# DigitalLabBoard_Traffic.net
KiCad netlist of a schematic drawn in Altium Designer
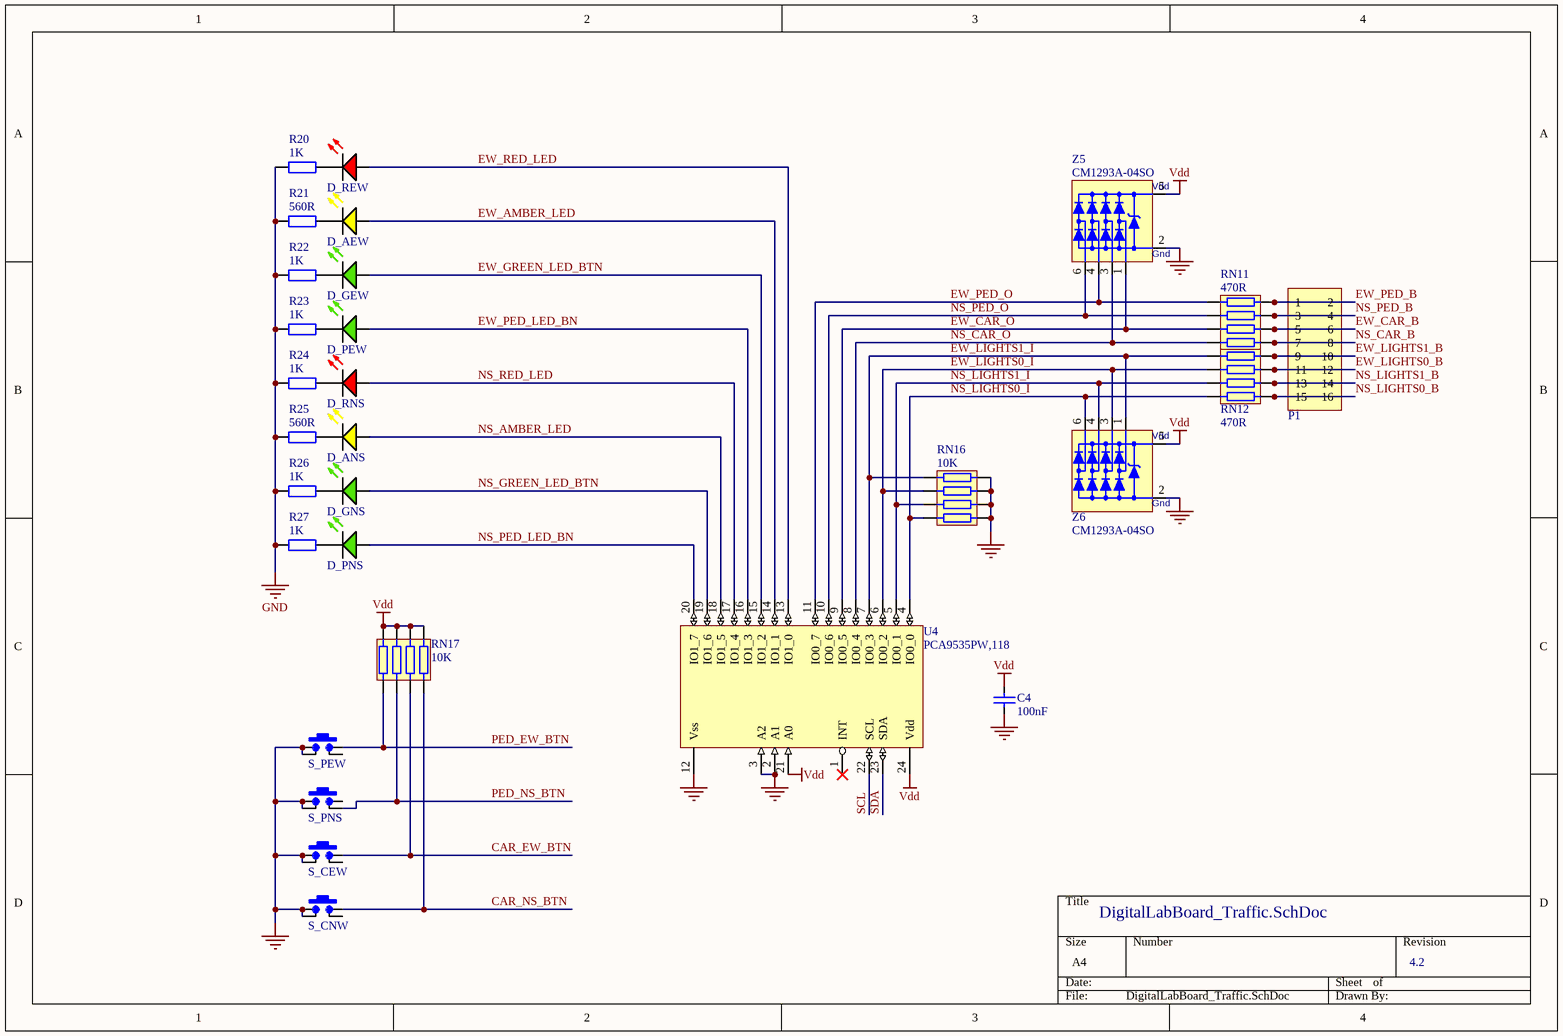
[diagram p0: DigitalLabBoard_Traffic.SchDoc]

(export (version "E")
  (design (tool "Eeschema 10.0.6"))
  (components
    (comp (ref "C4")
      (value "100nF")
      (footprint "CCNP1608-0603")
      (description "Capacitor non-polar SMT 0603")
      (fields
        (field (name "MANUFACTURER") "Generic Components")
        (field (name "PUBLISHER") "Altium Hobart Technology Centre")
      )
      (libsource (lib "MyLibrary") (part "Cap_CCNP_0603"))
    )
    (comp (ref "D_AEW")
      (value "LED Yellow")
      (footprint "LED1608-0603-Yellow")
      (description "LED 0603 Yellow")
      (fields (field (name "MANUFACTURER") "Generic Components") (field (name "PUBLISHER") "Altium Limited"))
      (libsource (lib "MySchLib") (part "LED-0603-Yellow"))
    )
    (comp (ref "D_ANS")
      (value "LED Yellow")
      (footprint "LED1608-0603-Yellow")
      (description "LED 0603 Yellow")
      (fields (field (name "MANUFACTURER") "Generic Components") (field (name "PUBLISHER") "Altium Limited"))
      (libsource (lib "MySchLib") (part "LED-0603-Yellow"))
    )
    (comp (ref "D_GEW")
      (value "LED Green")
      (footprint "LED1608-0603-GREEN")
      (description "LED 0603 Green")
      (fields (field (name "MANUFACTURER") "Generic Components") (field (name "PUBLISHER") "Altium Limited"))
      (libsource (lib "MySchLib") (part "LED-0603-Green"))
    )
    (comp (ref "D_GNS")
      (value "LED Green")
      (footprint "LED1608-0603-GREEN")
      (description "LED 0603 Green")
      (fields (field (name "MANUFACTURER") "Generic Components") (field (name "PUBLISHER") "Altium Limited"))
      (libsource (lib "MySchLib") (part "LED-0603-Green"))
    )
    (comp (ref "D_PEW")
      (value "LED Green")
      (footprint "LED1608-0603-GREEN")
      (description "LED 0603 Green")
      (fields (field (name "MANUFACTURER") "Generic Components") (field (name "PUBLISHER") "Altium Limited"))
      (libsource (lib "MySchLib") (part "LED-0603-Green"))
    )
    (comp (ref "D_PNS")
      (value "LED Green")
      (footprint "LED1608-0603-GREEN")
      (description "LED 0603 Green")
      (fields (field (name "MANUFACTURER") "Generic Components") (field (name "PUBLISHER") "Altium Limited"))
      (libsource (lib "MySchLib") (part "LED-0603-Green"))
    )
    (comp (ref "D_REW")
      (value "LED Red")
      (footprint "LED1608-0603-RED")
      (description "LED 0603 Red")
      (fields (field (name "MANUFACTURER") "Generic Components") (field (name "PUBLISHER") "Altium Limited"))
      (libsource (lib "MySchLib") (part "LED-0603-Red"))
    )
    (comp (ref "D_RNS")
      (value "LED Red")
      (footprint "LED1608-0603-RED")
      (description "LED 0603 Red")
      (fields (field (name "MANUFACTURER") "Generic Components") (field (name "PUBLISHER") "Altium Limited"))
      (libsource (lib "MySchLib") (part "LED-0603-Red"))
    )
    (comp (ref "P1")
      (value "Header 2x8")
      (footprint "HDR2X8S")
      (libsource (lib "MyLibrary") (part "Header 2x8"))
    )
    (comp (ref "R20")
      (value "1K")
      (footprint "CR1608-0603")
      (description "Resistor SMT 0603")
      (fields
        (field (name "MANUFACTURER") "Generic Components")
        (field (name "PUBLISHER") "Altium Hobart Technology Centre")
      )
      (libsource (lib "MyLibrary") (part "Res_CR0603"))
    )
    (comp (ref "R21")
      (value "560R")
      (footprint "CR1608-0603")
      (description "Resistor SMT 0603")
      (fields
        (field (name "MANUFACTURER") "Generic Components")
        (field (name "PUBLISHER") "Altium Hobart Technology Centre")
      )
      (libsource (lib "MyLibrary") (part "Res_CR0603"))
    )
    (comp (ref "R22")
      (value "1K")
      (footprint "CR1608-0603")
      (description "Resistor SMT 0603")
      (fields
        (field (name "MANUFACTURER") "Generic Components")
        (field (name "PUBLISHER") "Altium Hobart Technology Centre")
      )
      (libsource (lib "MyLibrary") (part "Res_CR0603"))
    )
    (comp (ref "R23")
      (value "1K")
      (footprint "CR1608-0603")
      (description "Resistor SMT 0603")
      (fields
        (field (name "MANUFACTURER") "Generic Components")
        (field (name "PUBLISHER") "Altium Hobart Technology Centre")
      )
      (libsource (lib "MyLibrary") (part "Res_CR0603"))
    )
    (comp (ref "R24")
      (value "1K")
      (footprint "CR1608-0603")
      (description "Resistor SMT 0603")
      (fields
        (field (name "MANUFACTURER") "Generic Components")
        (field (name "PUBLISHER") "Altium Hobart Technology Centre")
      )
      (libsource (lib "MyLibrary") (part "Res_CR0603"))
    )
    (comp (ref "R25")
      (value "560R")
      (footprint "CR1608-0603")
      (description "Resistor SMT 0603")
      (fields
        (field (name "MANUFACTURER") "Generic Components")
        (field (name "PUBLISHER") "Altium Hobart Technology Centre")
      )
      (libsource (lib "MyLibrary") (part "Res_CR0603"))
    )
    (comp (ref "R26")
      (value "1K")
      (footprint "CR1608-0603")
      (description "Resistor SMT 0603")
      (fields
        (field (name "MANUFACTURER") "Generic Components")
        (field (name "PUBLISHER") "Altium Hobart Technology Centre")
      )
      (libsource (lib "MyLibrary") (part "Res_CR0603"))
    )
    (comp (ref "R27")
      (value "1K")
      (footprint "CR1608-0603")
      (description "Resistor SMT 0603")
      (fields
        (field (name "MANUFACTURER") "Generic Components")
        (field (name "PUBLISHER") "Altium Hobart Technology Centre")
      )
      (libsource (lib "MyLibrary") (part "Res_CR0603"))
    )
    (comp (ref "RN11")
      (value "470R")
      (footprint "CR1206-0603_X4_N")
      (description "SMT x4 Resistor Array")
      (libsource (lib "MyLibrary") (part "ResistorNetwork_CR0603x4"))
    )
    (comp (ref "RN12")
      (value "470R")
      (footprint "CR1206-0603_X4_N")
      (description "SMT x4 Resistor Array")
      (libsource (lib "MyLibrary") (part "ResistorNetwork_CR0603x4"))
    )
    (comp (ref "RN16")
      (value "10K")
      (footprint "CR1206-0603_X4_N")
      (description "SMT x4 Resistor Array")
      (libsource (lib "MyLibrary") (part "ResistorNetwork_CR0603x4"))
    )
    (comp (ref "RN17")
      (value "10K")
      (footprint "CR1206-0603_X4_N")
      (description "SMT x4 Resistor Array")
      (libsource (lib "") (part "ResistorNetwork_CR0603x4_1"))
    )
    (comp (ref "S_CEW")
      (value "~")
      (footprint "SMD-SW-4_5.1x5.1x2.0_M")
      (description "Tactile Switch SPST 5.10mm X 5.10mm\r\n(1.5mm=C318884)\r\n(2.0mm=C318888)\r\n(3.5mm=C318886)")
      (libsource (lib "MySchLib") (part "SW_PB-TS"))
    )
    (comp (ref "S_CNW")
      (value "~")
      (footprint "SMD-SW-4_5.1x5.1x2.0_M")
      (description "Tactile Switch SPST 5.10mm X 5.10mm\r\n(1.5mm=C318884)\r\n(2.0mm=C318888)\r\n(3.5mm=C318886)")
      (libsource (lib "MySchLib") (part "SW_PB-TS"))
    )
    (comp (ref "S_PEW")
      (value "~")
      (footprint "SMD-SW-4_5.1x5.1x2.0_M")
      (description "Tactile Switch SPST 5.10mm X 5.10mm\r\n(1.5mm=C318884)\r\n(2.0mm=C318888)\r\n(3.5mm=C318886)")
      (libsource (lib "MySchLib") (part "SW_PB-TS"))
    )
    (comp (ref "S_PNS")
      (value "~")
      (footprint "SMD-SW-4_5.1x5.1x2.0_M")
      (description "Tactile Switch SPST 5.10mm X 5.10mm\r\n(1.5mm=C318884)\r\n(2.0mm=C318888)\r\n(3.5mm=C318886)")
      (libsource (lib "MySchLib") (part "SW_PB-TS"))
    )
    (comp (ref "U4")
      (value "PCA9535PW,118")
      (footprint "TSSOP24_N")
      (description "16-bit I2C I/O Expander (TSSOP24)\r\nNO PUPs on I/O pins")
      (libsource (lib "MySchLib") (part "PCA9535PW,118"))
    )
    (comp (ref "Z5")
      (value "CM1293A-04SO")
      (footprint "SOT457_N")
      (description "Ultra low capacitance quadruple rail-to-rail ESD protection")
      (libsource (lib "MySchLib") (part "CM1293A-04SO"))
    )
    (comp (ref "Z6")
      (value "CM1293A-04SO")
      (footprint "SOT457_N")
      (description "Ultra low capacitance quadruple rail-to-rail ESD protection")
      (libsource (lib "") (part "CM1293A-04SO_1"))
    )
  )
  (nets
    (net (code "1") (name "/CAR_EW_BTN") (class "Default")
      (node (ref "RN17") (pin "6") (pinfunction "6_6") (pintype "passive"))
      (node (ref "S_CEW") (pin "2b") (pinfunction "2b_2b") (pintype "passive"))
    )
    (net (code "2") (name "/CAR_NS_BTN") (class "Default")
      (node (ref "RN17") (pin "5") (pinfunction "5_5") (pintype "passive"))
      (node (ref "S_CNW") (pin "2b") (pinfunction "2b_2b") (pintype "passive"))
    )
    (net (code "3") (name "/EW_AMBER_LED") (class "Default")
      (node (ref "D_AEW") (pin "A") (pinfunction "A_A") (pintype "passive"))
      (node (ref "U4") (pin "14") (pinfunction "IO1_1_14") (pintype "bidirectional"))
    )
    (net (code "4") (name "/EW_CAR_B") (class "Default")
      (node (ref "P1") (pin "5") (pinfunction "5_5") (pintype "passive"))
      (node (ref "P1") (pin "6") (pinfunction "6_6") (pintype "passive"))
      (node (ref "RN11") (pin "7") (pinfunction "7_7") (pintype "passive"))
    )
    (net (code "5") (name "/EW_CAR_O") (class "Default")
      (node (ref "RN11") (pin "2") (pinfunction "2_2") (pintype "passive"))
      (node (ref "U4") (pin "9") (pinfunction "IO0_5_9") (pintype "bidirectional"))
      (node (ref "Z5") (pin "1") (pintype "passive"))
    )
    (net (code "6") (name "/EW_GREEN_LED_BTN") (class "Default")
      (node (ref "D_GEW") (pin "A") (pinfunction "A_A") (pintype "passive"))
      (node (ref "U4") (pin "15") (pinfunction "IO1_2_15") (pintype "bidirectional"))
    )
    (net (code "7") (name "/EW_LIGHTS0_B") (class "Default")
      (node (ref "P1") (pin "11") (pinfunction "11_11") (pintype "passive"))
      (node (ref "P1") (pin "12") (pinfunction "12_12") (pintype "passive"))
      (node (ref "RN12") (pin "6") (pinfunction "6_6") (pintype "passive"))
    )
    (net (code "8") (name "/EW_LIGHTS0_I") (class "Default")
      (node (ref "RN12") (pin "3") (pinfunction "3_3") (pintype "passive"))
      (node (ref "RN16") (pin "3") (pinfunction "3_3") (pintype "passive"))
      (node (ref "U4") (pin "6") (pinfunction "IO0_2_6") (pintype "bidirectional"))
      (node (ref "Z6") (pin "3") (pintype "passive"))
    )
    (net (code "9") (name "/EW_LIGHTS1_B") (class "Default")
      (node (ref "P1") (pin "10") (pinfunction "10_10") (pintype "passive"))
      (node (ref "P1") (pin "9") (pinfunction "9_9") (pintype "passive"))
      (node (ref "RN12") (pin "5") (pinfunction "5_5") (pintype "passive"))
    )
    (net (code "10") (name "/EW_LIGHTS1_I") (class "Default")
      (node (ref "RN12") (pin "4") (pinfunction "4_4") (pintype "passive"))
      (node (ref "RN16") (pin "4") (pinfunction "4_4") (pintype "passive"))
      (node (ref "U4") (pin "7") (pinfunction "IO0_3_7") (pintype "bidirectional"))
      (node (ref "Z6") (pin "1") (pintype "passive"))
    )
    (net (code "11") (name "/EW_PED_B") (class "Default")
      (node (ref "P1") (pin "1") (pinfunction "1_1") (pintype "passive"))
      (node (ref "P1") (pin "2") (pinfunction "2_2") (pintype "passive"))
      (node (ref "RN11") (pin "5") (pinfunction "5_5") (pintype "passive"))
    )
    (net (code "12") (name "/EW_PED_LED_BN") (class "Default")
      (node (ref "D_PEW") (pin "A") (pinfunction "A_A") (pintype "passive"))
      (node (ref "U4") (pin "16") (pinfunction "IO1_3_16") (pintype "bidirectional"))
    )
    (net (code "13") (name "/EW_PED_O") (class "Default")
      (node (ref "RN11") (pin "4") (pinfunction "4_4") (pintype "passive"))
      (node (ref "U4") (pin "11") (pinfunction "IO0_7_11") (pintype "bidirectional"))
      (node (ref "Z5") (pin "4") (pintype "passive"))
    )
    (net (code "14") (name "/EW_RED_LED") (class "Default")
      (node (ref "D_REW") (pin "A") (pinfunction "A_A") (pintype "passive"))
      (node (ref "U4") (pin "13") (pinfunction "IO1_0_13") (pintype "bidirectional"))
    )
    (net (code "15") (name "/NS_AMBER_LED") (class "Default")
      (node (ref "D_ANS") (pin "A") (pinfunction "A_A") (pintype "passive"))
      (node (ref "U4") (pin "18") (pinfunction "IO1_5_18") (pintype "bidirectional"))
    )
    (net (code "16") (name "/NS_CAR_B") (class "Default")
      (node (ref "P1") (pin "7") (pinfunction "7_7") (pintype "passive"))
      (node (ref "P1") (pin "8") (pinfunction "8_8") (pintype "passive"))
      (node (ref "RN11") (pin "8") (pinfunction "8_8") (pintype "passive"))
    )
    (net (code "17") (name "/NS_CAR_O") (class "Default")
      (node (ref "RN11") (pin "1") (pinfunction "1_1") (pintype "passive"))
      (node (ref "U4") (pin "8") (pinfunction "IO0_4_8") (pintype "bidirectional"))
      (node (ref "Z5") (pin "3") (pintype "passive"))
    )
    (net (code "18") (name "/NS_GREEN_LED_BTN") (class "Default")
      (node (ref "D_GNS") (pin "A") (pinfunction "A_A") (pintype "passive"))
      (node (ref "U4") (pin "19") (pinfunction "IO1_6_19") (pintype "bidirectional"))
    )
    (net (code "19") (name "/NS_LIGHTS0_B") (class "Default")
      (node (ref "P1") (pin "15") (pinfunction "15_15") (pintype "passive"))
      (node (ref "P1") (pin "16") (pinfunction "16_16") (pintype "passive"))
      (node (ref "RN12") (pin "8") (pinfunction "8_8") (pintype "passive"))
    )
    (net (code "20") (name "/NS_LIGHTS0_I") (class "Default")
      (node (ref "RN12") (pin "1") (pinfunction "1_1") (pintype "passive"))
      (node (ref "RN16") (pin "1") (pinfunction "1_1") (pintype "passive"))
      (node (ref "U4") (pin "4") (pinfunction "IO0_0_4") (pintype "bidirectional"))
      (node (ref "Z6") (pin "6") (pintype "passive"))
    )
    (net (code "21") (name "/NS_LIGHTS1_B") (class "Default")
      (node (ref "P1") (pin "13") (pinfunction "13_13") (pintype "passive"))
      (node (ref "P1") (pin "14") (pinfunction "14_14") (pintype "passive"))
      (node (ref "RN12") (pin "7") (pinfunction "7_7") (pintype "passive"))
    )
    (net (code "22") (name "/NS_LIGHTS1_I") (class "Default")
      (node (ref "RN12") (pin "2") (pinfunction "2_2") (pintype "passive"))
      (node (ref "RN16") (pin "2") (pinfunction "2_2") (pintype "passive"))
      (node (ref "U4") (pin "5") (pinfunction "IO0_1_5") (pintype "bidirectional"))
      (node (ref "Z6") (pin "4") (pintype "passive"))
    )
    (net (code "23") (name "/NS_PED_B") (class "Default")
      (node (ref "P1") (pin "3") (pinfunction "3_3") (pintype "passive"))
      (node (ref "P1") (pin "4") (pinfunction "4_4") (pintype "passive"))
      (node (ref "RN11") (pin "6") (pinfunction "6_6") (pintype "passive"))
    )
    (net (code "24") (name "/NS_PED_LED_BN") (class "Default")
      (node (ref "D_PNS") (pin "A") (pinfunction "A_A") (pintype "passive"))
      (node (ref "U4") (pin "20") (pinfunction "IO1_7_20") (pintype "bidirectional"))
    )
    (net (code "25") (name "/NS_PED_O") (class "Default")
      (node (ref "RN11") (pin "3") (pinfunction "3_3") (pintype "passive"))
      (node (ref "U4") (pin "10") (pinfunction "IO0_6_10") (pintype "bidirectional"))
      (node (ref "Z5") (pin "6") (pintype "passive"))
    )
    (net (code "26") (name "/NS_RED_LED") (class "Default")
      (node (ref "D_RNS") (pin "A") (pinfunction "A_A") (pintype "passive"))
      (node (ref "U4") (pin "17") (pinfunction "IO1_4_17") (pintype "bidirectional"))
    )
    (net (code "27") (name "/PED_EW_BTN") (class "Default")
      (node (ref "RN17") (pin "8") (pinfunction "8_8") (pintype "passive"))
      (node (ref "S_PEW") (pin "1b") (pinfunction "1b_1b") (pintype "passive"))
    )
    (net (code "28") (name "/PED_NS_BTN") (class "Default")
      (node (ref "RN17") (pin "7") (pinfunction "7_7") (pintype "passive"))
      (node (ref "S_PNS") (pin "2") (pinfunction "2_2") (pintype "passive"))
    )
    (net (code "29") (name "/SCL") (class "Default")
      (node (ref "U4") (pin "22") (pinfunction "SCL_22") (pintype "bidirectional"))
    )
    (net (code "30") (name "/SDA") (class "Default")
      (node (ref "U4") (pin "23") (pinfunction "SDA_23") (pintype "bidirectional"))
    )
    (net (code "31") (name "GND") (class "Default")
      (node (ref "C4") (pin "1") (pinfunction "1_1") (pintype "passive"))
      (node (ref "R20") (pin "1") (pinfunction "1_1") (pintype "passive"))
      (node (ref "R21") (pin "1") (pinfunction "1_1") (pintype "passive"))
      (node (ref "R22") (pin "1") (pinfunction "1_1") (pintype "passive"))
      (node (ref "R23") (pin "1") (pinfunction "1_1") (pintype "passive"))
      (node (ref "R24") (pin "1") (pinfunction "1_1") (pintype "passive"))
      (node (ref "R25") (pin "1") (pinfunction "1_1") (pintype "passive"))
      (node (ref "R26") (pin "1") (pinfunction "1_1") (pintype "passive"))
      (node (ref "R27") (pin "1") (pinfunction "1_1") (pintype "passive"))
      (node (ref "RN16") (pin "5") (pinfunction "5_5") (pintype "passive"))
      (node (ref "RN16") (pin "6") (pinfunction "6_6") (pintype "passive"))
      (node (ref "RN16") (pin "7") (pinfunction "7_7") (pintype "passive"))
      (node (ref "RN16") (pin "8") (pinfunction "8_8") (pintype "passive"))
      (node (ref "S_CEW") (pin "1") (pinfunction "1_1") (pintype "passive"))
      (node (ref "S_CEW") (pin "1b") (pinfunction "1b_1b") (pintype "passive"))
      (node (ref "S_CNW") (pin "1") (pinfunction "1_1") (pintype "passive"))
      (node (ref "S_CNW") (pin "1b") (pinfunction "1b_1b") (pintype "passive"))
      (node (ref "S_PEW") (pin "2") (pinfunction "2_2") (pintype "passive"))
      (node (ref "S_PEW") (pin "2b") (pinfunction "2b_2b") (pintype "passive"))
      (node (ref "S_PNS") (pin "1") (pinfunction "1_1") (pintype "passive"))
      (node (ref "S_PNS") (pin "1b") (pinfunction "1b_1b") (pintype "passive"))
      (node (ref "U4") (pin "12") (pinfunction "Vss_12") (pintype "power_in"))
      (node (ref "U4") (pin "2") (pinfunction "A1_2") (pintype "input"))
      (node (ref "U4") (pin "3") (pinfunction "A2_3") (pintype "input"))
      (node (ref "Z5") (pin "2") (pinfunction "Vn_2") (pintype "passive"))
      (node (ref "Z6") (pin "2") (pinfunction "Vn_2") (pintype "passive"))
    )
    (net (code "32") (name "Net-(D_AEW-PadK)") (class "Default")
      (node (ref "D_AEW") (pin "K") (pinfunction "K_K") (pintype "passive"))
      (node (ref "R21") (pin "2") (pinfunction "2_2") (pintype "passive"))
    )
    (net (code "33") (name "Net-(D_ANS-PadK)") (class "Default")
      (node (ref "D_ANS") (pin "K") (pinfunction "K_K") (pintype "passive"))
      (node (ref "R25") (pin "2") (pinfunction "2_2") (pintype "passive"))
    )
    (net (code "34") (name "Net-(D_GEW-PadK)") (class "Default")
      (node (ref "D_GEW") (pin "K") (pinfunction "K_K") (pintype "passive"))
      (node (ref "R22") (pin "2") (pinfunction "2_2") (pintype "passive"))
    )
    (net (code "35") (name "Net-(D_GNS-PadK)") (class "Default")
      (node (ref "D_GNS") (pin "K") (pinfunction "K_K") (pintype "passive"))
      (node (ref "R26") (pin "2") (pinfunction "2_2") (pintype "passive"))
    )
    (net (code "36") (name "Net-(D_PEW-PadK)") (class "Default")
      (node (ref "D_PEW") (pin "K") (pinfunction "K_K") (pintype "passive"))
      (node (ref "R23") (pin "2") (pinfunction "2_2") (pintype "passive"))
    )
    (net (code "37") (name "Net-(D_PNS-PadK)") (class "Default")
      (node (ref "D_PNS") (pin "K") (pinfunction "K_K") (pintype "passive"))
      (node (ref "R27") (pin "2") (pinfunction "2_2") (pintype "passive"))
    )
    (net (code "38") (name "Net-(D_REW-PadK)") (class "Default")
      (node (ref "D_REW") (pin "K") (pinfunction "K_K") (pintype "passive"))
      (node (ref "R20") (pin "2") (pinfunction "2_2") (pintype "passive"))
    )
    (net (code "39") (name "Net-(D_RNS-PadK)") (class "Default")
      (node (ref "D_RNS") (pin "K") (pinfunction "K_K") (pintype "passive"))
      (node (ref "R24") (pin "2") (pinfunction "2_2") (pintype "passive"))
    )
    (net (code "40") (name "Vdd") (class "Default")
      (node (ref "C4") (pin "2") (pinfunction "2_2") (pintype "passive"))
      (node (ref "RN17") (pin "1") (pinfunction "1_1") (pintype "passive"))
      (node (ref "RN17") (pin "2") (pinfunction "2_2") (pintype "passive"))
      (node (ref "RN17") (pin "3") (pinfunction "3_3") (pintype "passive"))
      (node (ref "RN17") (pin "4") (pinfunction "4_4") (pintype "passive"))
      (node (ref "U4") (pin "21") (pinfunction "A0_21") (pintype "input"))
      (node (ref "U4") (pin "24") (pinfunction "Vdd_24") (pintype "power_in"))
      (node (ref "Z5") (pin "5") (pinfunction "Vp_5") (pintype "passive"))
      (node (ref "Z6") (pin "5") (pinfunction "Vp_5") (pintype "passive"))
    )
    (net (code "41") (name "unconnected-(S_CEW-Pad2)") (class "Default")
      (node (ref "S_CEW") (pin "2") (pinfunction "2_2") (pintype "passive"))
    )
    (net (code "42") (name "unconnected-(S_CNW-Pad2)") (class "Default")
      (node (ref "S_CNW") (pin "2") (pinfunction "2_2") (pintype "passive"))
    )
    (net (code "43") (name "unconnected-(S_PEW-Pad1)") (class "Default")
      (node (ref "S_PEW") (pin "1") (pinfunction "1_1") (pintype "passive"))
    )
    (net (code "44") (name "unconnected-(S_PNS-Pad2b)") (class "Default")
      (node (ref "S_PNS") (pin "2b") (pinfunction "2b_2b") (pintype "passive"))
    )
    (net (code "45") (name "unconnected-(U4-INT-Pad1)") (class "Default")
      (node (ref "U4") (pin "1") (pinfunction "INT_1") (pintype "open_collector+no_connect"))
    )
  )
)
